# YMF_262.net
KiCad netlist of a schematic drawn in EAGLE
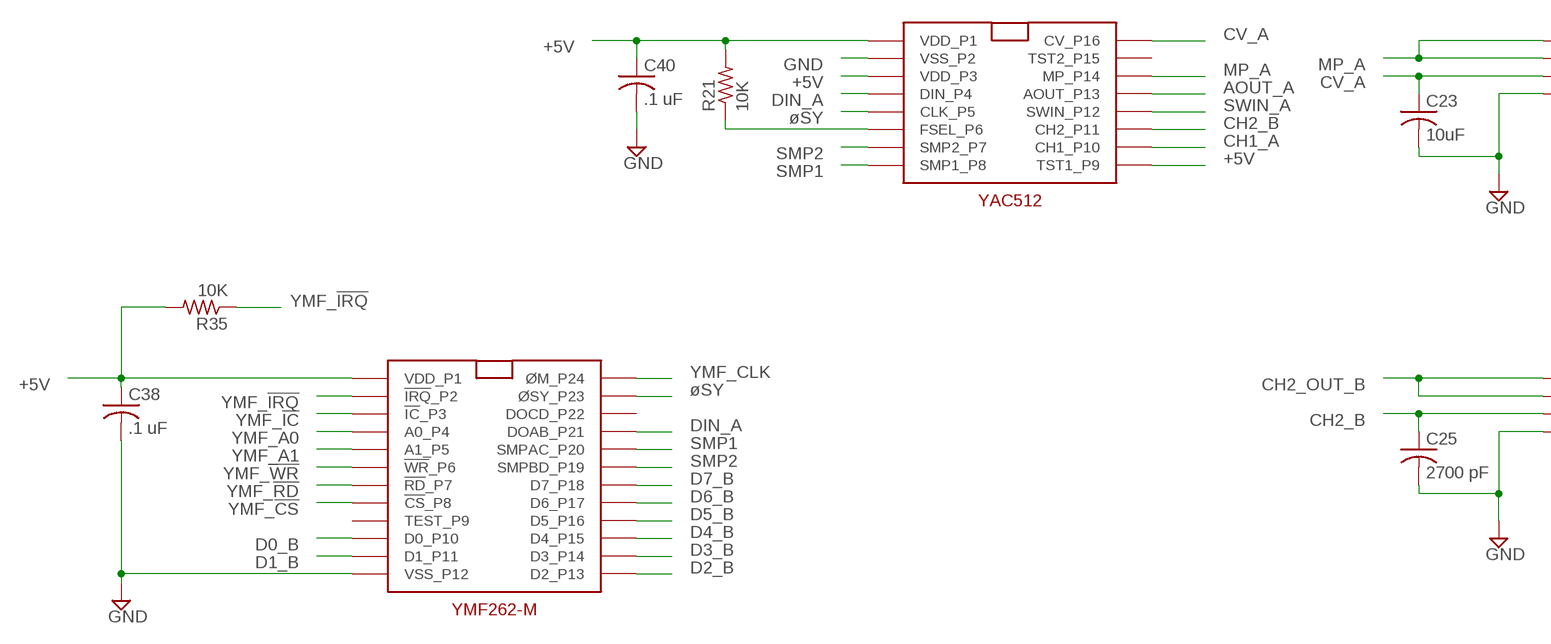
[diagram p0: schematic, sheet 1, part 1 of 2]
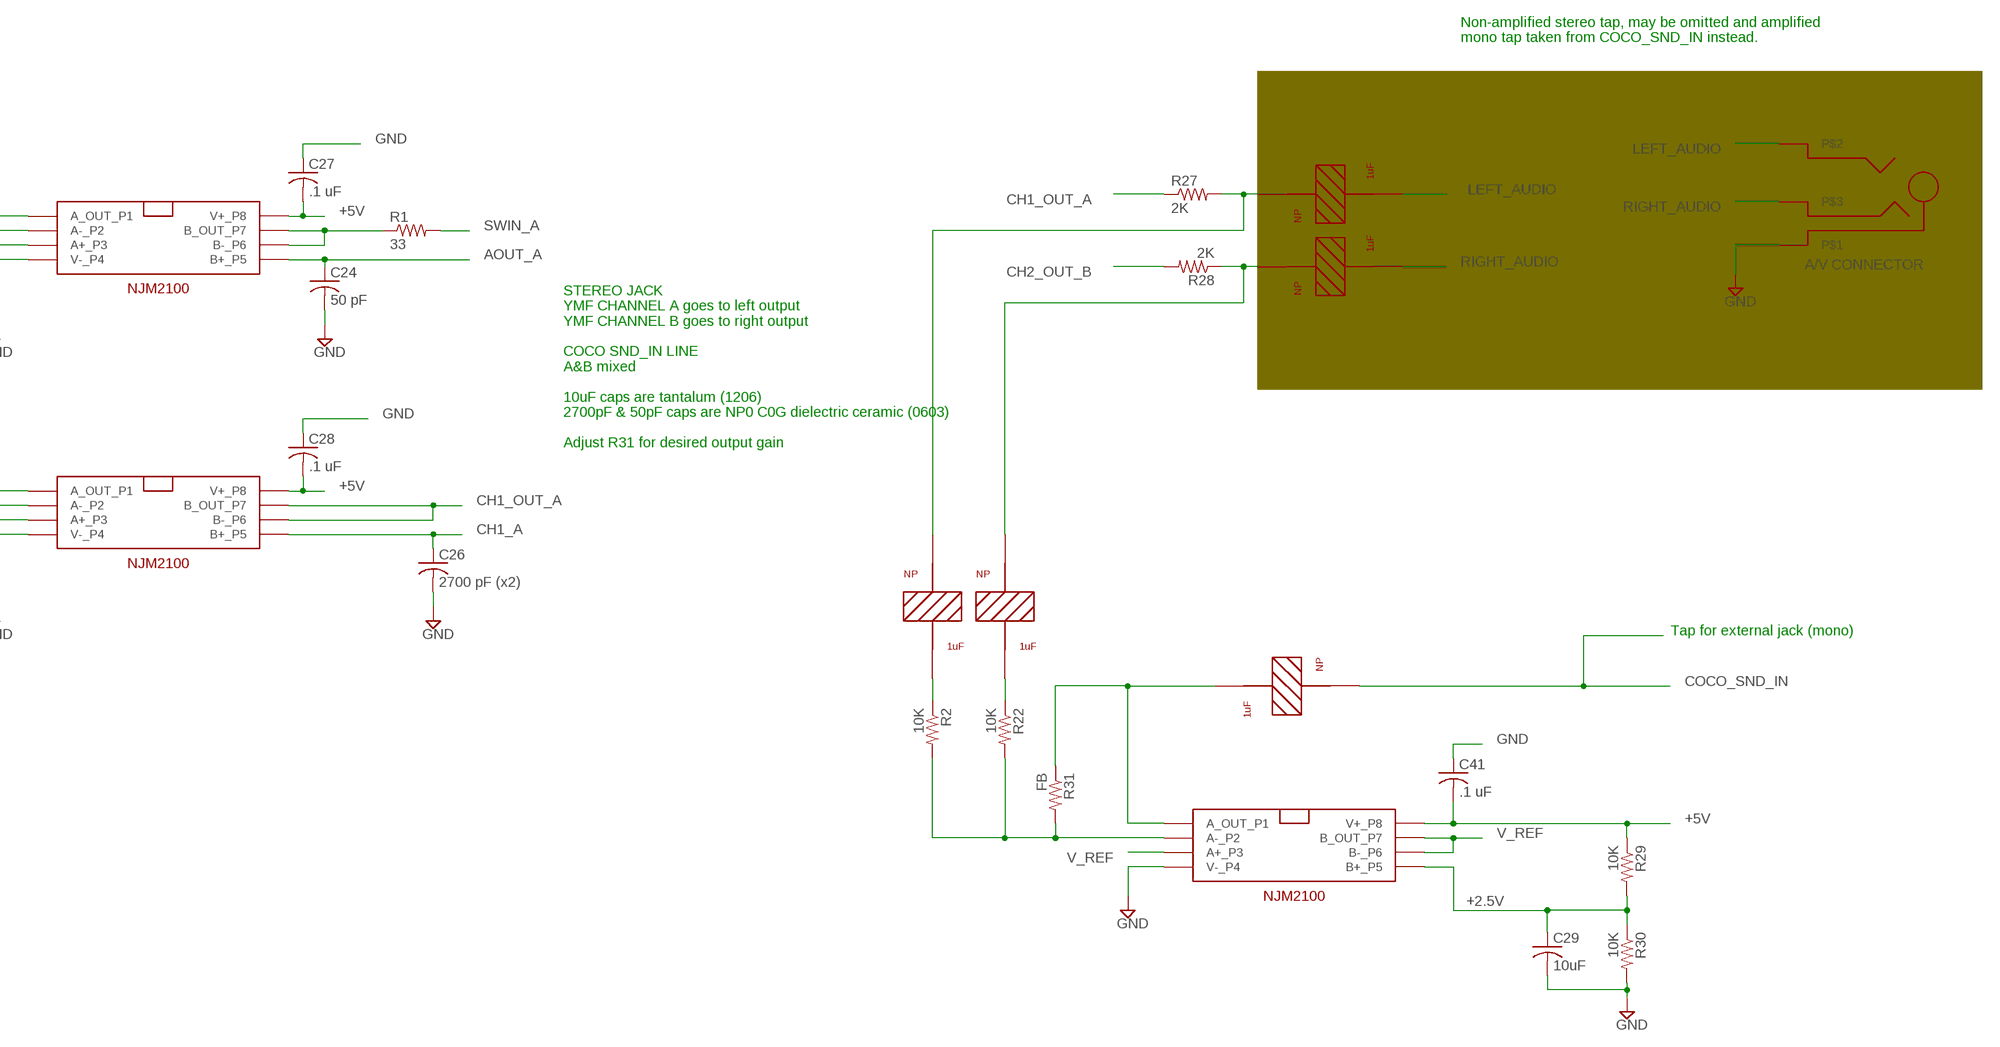
[diagram p1: schematic, sheet 1, part 2 of 2]

(export (version "E")
  (design (tool "Eeschema 10.0.6"))
  (components
    (comp (ref "C23")
      (value "10uF")
      (footprint "eagle-import:C1206")
      (libsource (lib "eagle-import") (part "C-USC1206"))
    )
    (comp (ref "C24")
      (value "50 pF")
      (footprint "eagle-import:C0603K")
      (libsource (lib "eagle-import") (part "C-USC0603K"))
    )
    (comp (ref "C25")
      (value "2700 pF")
      (footprint "eagle-import:C0603K")
      (libsource (lib "eagle-import") (part "C-USC0603K"))
    )
    (comp (ref "C26")
      (value "2700 pF (x2)")
      (footprint "eagle-import:C0603K")
      (libsource (lib "eagle-import") (part "C-USC0603K"))
    )
    (comp (ref "C27")
      (value ".1 uF")
      (footprint "eagle-import:C0603K")
      (libsource (lib "eagle-import") (part "C-USC0603K"))
    )
    (comp (ref "C28")
      (value ".1 uF")
      (footprint "eagle-import:C0603K")
      (libsource (lib "eagle-import") (part "C-USC0603K"))
    )
    (comp (ref "C29")
      (value "10uF")
      (footprint "eagle-import:C1206")
      (libsource (lib "eagle-import") (part "C-USC1206"))
    )
    (comp (ref "C38")
      (value ".1 uF")
      (footprint "eagle-import:C0603K")
      (libsource (lib "eagle-import") (part "C-USC0603K"))
    )
    (comp (ref "C40")
      (value ".1 uF")
      (footprint "eagle-import:C0603K")
      (libsource (lib "eagle-import") (part "C-USC0603K"))
    )
    (comp (ref "C41")
      (value ".1 uF")
      (footprint "eagle-import:C0603K")
      (libsource (lib "eagle-import") (part "C-USC0603K"))
    )
    (comp (ref "R1")
      (value "33")
      (footprint "eagle-import:R0805")
      (libsource (lib "eagle-import") (part "R-US_R0805"))
    )
    (comp (ref "R2")
      (value "10K")
      (footprint "eagle-import:R0805")
      (libsource (lib "eagle-import") (part "R-US_R0805"))
    )
    (comp (ref "R21")
      (value "10K")
      (footprint "eagle-import:M0805")
      (libsource (lib "eagle-import") (part "R-US_M0805"))
    )
    (comp (ref "R22")
      (value "10K")
      (footprint "eagle-import:R0805")
      (libsource (lib "eagle-import") (part "R-US_R0805"))
    )
    (comp (ref "R27")
      (value "2K")
      (footprint "eagle-import:R0805")
      (libsource (lib "eagle-import") (part "R-US_R0805"))
    )
    (comp (ref "R28")
      (value "2K")
      (footprint "eagle-import:R0805")
      (libsource (lib "eagle-import") (part "R-US_R0805"))
    )
    (comp (ref "R29")
      (value "10K")
      (footprint "eagle-import:R0805")
      (libsource (lib "eagle-import") (part "R-US_R0805"))
    )
    (comp (ref "R30")
      (value "10K")
      (footprint "eagle-import:R0805")
      (libsource (lib "eagle-import") (part "R-US_R0805"))
    )
    (comp (ref "R31")
      (value "FB")
      (footprint "eagle-import:R0805")
      (libsource (lib "eagle-import") (part "R-US_R0805"))
    )
    (comp (ref "R35")
      (value "10K")
      (footprint "eagle-import:M0805")
      (libsource (lib "eagle-import") (part "R-US_M0805"))
    )
    (comp (ref "U$1")
      (value "1uF")
      (footprint "eagle-import:NICHICON_SMT_CAP_4MM_NP")
      (libsource (lib "eagle-import") (part "NICHICON_SMT_CAP_4MM_NP"))
    )
    (comp (ref "U$2")
      (value "CUI-3543N")
      (footprint "eagle-import:CUI-3543N")
      (libsource (lib "eagle-import") (part "CUI-3543N"))
    )
    (comp (ref "U$3")
      (value "1uF")
      (footprint "eagle-import:NICHICON_SMT_CAP_4MM_NP")
      (libsource (lib "eagle-import") (part "NICHICON_SMT_CAP_4MM_NP"))
    )
    (comp (ref "U$15")
      (value "YMF262_M")
      (footprint "eagle-import:YMF262_M")
      (libsource (lib "eagle-import") (part "YMF262_M"))
    )
    (comp (ref "U$18")
      (value "YAC512")
      (footprint "eagle-import:YAC512")
      (libsource (lib "eagle-import") (part "YAC512"))
    )
    (comp (ref "U$19")
      (value "NJM2100_SSOP8")
      (footprint "eagle-import:NJM2100_SSOP8")
      (libsource (lib "eagle-import") (part "NJM2100_SSOP8"))
    )
    (comp (ref "U$20")
      (value "NJM2100_SSOP8")
      (footprint "eagle-import:NJM2100_SSOP8")
      (libsource (lib "eagle-import") (part "NJM2100_SSOP8"))
    )
    (comp (ref "U$21")
      (value "1uF")
      (footprint "eagle-import:NICHICON_SMT_CAP_4MM_NP")
      (libsource (lib "eagle-import") (part "NICHICON_SMT_CAP_4MM_NP"))
    )
    (comp (ref "U$25")
      (value "NJM2100_SSOP8")
      (footprint "eagle-import:NJM2100_SSOP8")
      (libsource (lib "eagle-import") (part "NJM2100_SSOP8"))
    )
    (comp (ref "U$26")
      (value "1uF")
      (footprint "eagle-import:NICHICON_SMT_CAP_4MM_NP")
      (libsource (lib "eagle-import") (part "NICHICON_SMT_CAP_4MM_NP"))
    )
    (comp (ref "U$27")
      (value "1uF")
      (footprint "eagle-import:NICHICON_SMT_CAP_4MM_NP")
      (libsource (lib "eagle-import") (part "NICHICON_SMT_CAP_4MM_NP"))
    )
  )
  (nets
    (net (code "1") (name "/+2.5V") (class "Default")
      (node (ref "C29") (pin "1") (pinfunction "1_1") (pintype "passive"))
      (node (ref "R29") (pin "2") (pinfunction "2_2") (pintype "passive"))
      (node (ref "R30") (pin "1") (pinfunction "1_1") (pintype "passive"))
      (node (ref "U$25") (pin "P$5") (pinfunction "B+_P5_P$5") (pintype "bidirectional"))
    )
    (net (code "2") (name "/+5V") (class "Default")
      (node (ref "C27") (pin "2") (pinfunction "2_2") (pintype "passive"))
      (node (ref "C28") (pin "2") (pinfunction "2_2") (pintype "passive"))
      (node (ref "C38") (pin "1") (pinfunction "1_1") (pintype "passive"))
      (node (ref "C40") (pin "1") (pinfunction "1_1") (pintype "passive"))
      (node (ref "C41") (pin "2") (pinfunction "2_2") (pintype "passive"))
      (node (ref "R21") (pin "2") (pinfunction "2_2") (pintype "passive"))
      (node (ref "R29") (pin "1") (pinfunction "1_1") (pintype "passive"))
      (node (ref "R35") (pin "2") (pinfunction "2_2") (pintype "passive"))
      (node (ref "U$15") (pin "P$1") (pinfunction "VDD_P1_P$1") (pintype "bidirectional"))
      (node (ref "U$18") (pin "P$1") (pinfunction "VDD_P1_P$1") (pintype "bidirectional"))
      (node (ref "U$18") (pin "P$3") (pinfunction "VDD_P3_P$3") (pintype "bidirectional"))
      (node (ref "U$18") (pin "P$9") (pinfunction "TST1_P9_P$9") (pintype "bidirectional"))
      (node (ref "U$19") (pin "P$8") (pinfunction "V+_P8_P$8") (pintype "bidirectional"))
      (node (ref "U$20") (pin "P$8") (pinfunction "V+_P8_P$8") (pintype "bidirectional"))
      (node (ref "U$25") (pin "P$8") (pinfunction "V+_P8_P$8") (pintype "bidirectional"))
    )
    (net (code "3") (name "/AOUT_A") (class "Default")
      (node (ref "C24") (pin "1") (pinfunction "1_1") (pintype "passive"))
      (node (ref "U$18") (pin "P$13") (pinfunction "AOUT_P13_P$13") (pintype "bidirectional"))
      (node (ref "U$19") (pin "P$5") (pinfunction "B+_P5_P$5") (pintype "bidirectional"))
    )
    (net (code "4") (name "/CH1_A") (class "Default")
      (node (ref "C26") (pin "1") (pinfunction "1_1") (pintype "passive"))
      (node (ref "U$18") (pin "P$10") (pinfunction "CH1_P10_P$10") (pintype "bidirectional"))
      (node (ref "U$20") (pin "P$5") (pinfunction "B+_P5_P$5") (pintype "bidirectional"))
    )
    (net (code "5") (name "/CH1_OUT_A") (class "Default")
      (node (ref "R27") (pin "1") (pinfunction "1_1") (pintype "passive"))
      (node (ref "U$20") (pin "P$6") (pinfunction "B-_P6_P$6") (pintype "bidirectional"))
      (node (ref "U$20") (pin "P$7") (pinfunction "B_OUT_P7_P$7") (pintype "bidirectional"))
    )
    (net (code "6") (name "/CH2_B") (class "Default")
      (node (ref "C25") (pin "1") (pinfunction "1_1") (pintype "passive"))
      (node (ref "U$18") (pin "P$11") (pinfunction "CH2_P11_P$11") (pintype "bidirectional"))
      (node (ref "U$20") (pin "P$3") (pinfunction "A+_P3_P$3") (pintype "bidirectional"))
    )
    (net (code "7") (name "/CH2_OUT_B") (class "Default")
      (node (ref "R28") (pin "2") (pinfunction "2_2") (pintype "passive"))
      (node (ref "U$20") (pin "P$1") (pinfunction "A_OUT_P1_P$1") (pintype "bidirectional"))
      (node (ref "U$20") (pin "P$2") (pinfunction "A-_P2_P$2") (pintype "bidirectional"))
    )
    (net (code "8") (name "/COCO_SND_IN") (class "Default")
      (node (ref "U$1") (pin "P$1") (pinfunction "P$1_P$1") (pintype "bidirectional"))
    )
    (net (code "9") (name "/CV_A") (class "Default")
      (node (ref "C23") (pin "1") (pinfunction "1_1") (pintype "passive"))
      (node (ref "U$18") (pin "P$16") (pinfunction "CV_P16_P$16") (pintype "bidirectional"))
      (node (ref "U$19") (pin "P$3") (pinfunction "A+_P3_P$3") (pintype "bidirectional"))
    )
    (net (code "10") (name "/D0_B") (class "Default")
      (node (ref "U$15") (pin "P$10") (pinfunction "D0_P10_P$10") (pintype "bidirectional"))
    )
    (net (code "11") (name "/D1_B") (class "Default")
      (node (ref "U$15") (pin "P$11") (pinfunction "D1_P11_P$11") (pintype "bidirectional"))
    )
    (net (code "12") (name "/D2_B") (class "Default")
      (node (ref "U$15") (pin "P$13") (pinfunction "D2_P13_P$13") (pintype "bidirectional"))
    )
    (net (code "13") (name "/D3_B") (class "Default")
      (node (ref "U$15") (pin "P$14") (pinfunction "D3_P14_P$14") (pintype "bidirectional"))
    )
    (net (code "14") (name "/D4_B") (class "Default")
      (node (ref "U$15") (pin "P$15") (pinfunction "D4_P15_P$15") (pintype "bidirectional"))
    )
    (net (code "15") (name "/D5_B") (class "Default")
      (node (ref "U$15") (pin "P$16") (pinfunction "D5_P16_P$16") (pintype "bidirectional"))
    )
    (net (code "16") (name "/D6_B") (class "Default")
      (node (ref "U$15") (pin "P$17") (pinfunction "D6_P17_P$17") (pintype "bidirectional"))
    )
    (net (code "17") (name "/D7_B") (class "Default")
      (node (ref "U$15") (pin "P$18") (pinfunction "D7_P18_P$18") (pintype "bidirectional"))
    )
    (net (code "18") (name "/DIN_A") (class "Default")
      (node (ref "U$15") (pin "P$21") (pinfunction "DOAB_P21_P$21") (pintype "bidirectional"))
      (node (ref "U$18") (pin "P$4") (pinfunction "DIN_P4_P$4") (pintype "bidirectional"))
    )
    (net (code "19") (name "/LEFT_AUDIO") (class "Default")
      (node (ref "U$2") (pin "2") (pinfunction "P$2_2") (pintype "bidirectional"))
      (node (ref "U$26") (pin "P$2") (pinfunction "P$2_P$2") (pintype "bidirectional"))
    )
    (net (code "20") (name "/MP_A") (class "Default")
      (node (ref "U$18") (pin "P$14") (pinfunction "MP_P14_P$14") (pintype "bidirectional"))
      (node (ref "U$19") (pin "P$1") (pinfunction "A_OUT_P1_P$1") (pintype "bidirectional"))
      (node (ref "U$19") (pin "P$2") (pinfunction "A-_P2_P$2") (pintype "bidirectional"))
    )
    (net (code "21") (name "/RIGHT_AUDIO") (class "Default")
      (node (ref "U$2") (pin "3") (pinfunction "P$3_3") (pintype "bidirectional"))
      (node (ref "U$27") (pin "P$2") (pinfunction "P$2_P$2") (pintype "bidirectional"))
    )
    (net (code "22") (name "/SMP1") (class "Default")
      (node (ref "U$15") (pin "P$20") (pinfunction "SMPAC_P20_P$20") (pintype "bidirectional"))
      (node (ref "U$18") (pin "P$8") (pinfunction "SMP1_P8_P$8") (pintype "bidirectional"))
    )
    (net (code "23") (name "/SMP2") (class "Default")
      (node (ref "U$15") (pin "P$19") (pinfunction "SMPBD_P19_P$19") (pintype "bidirectional"))
      (node (ref "U$18") (pin "P$7") (pinfunction "SMP2_P7_P$7") (pintype "bidirectional"))
    )
    (net (code "24") (name "/SWIN_A") (class "Default")
      (node (ref "R1") (pin "2") (pinfunction "2_2") (pintype "passive"))
      (node (ref "U$18") (pin "P$12") (pinfunction "SWIN_P12_P$12") (pintype "bidirectional"))
    )
    (net (code "25") (name "/V_REF") (class "Default")
      (node (ref "U$25") (pin "P$3") (pinfunction "A+_P3_P$3") (pintype "bidirectional"))
      (node (ref "U$25") (pin "P$6") (pinfunction "B-_P6_P$6") (pintype "bidirectional"))
      (node (ref "U$25") (pin "P$7") (pinfunction "B_OUT_P7_P$7") (pintype "bidirectional"))
    )
    (net (code "26") (name "/YMF_A0") (class "Default")
      (node (ref "U$15") (pin "P$4") (pinfunction "A0_P4_P$4") (pintype "bidirectional"))
    )
    (net (code "27") (name "/YMF_A1") (class "Default")
      (node (ref "U$15") (pin "P$5") (pinfunction "A1_P5_P$5") (pintype "bidirectional"))
    )
    (net (code "28") (name "/YMF_CLK") (class "Default")
      (node (ref "U$15") (pin "P$24") (pinfunction "ØM_P24_P$24") (pintype "bidirectional"))
    )
    (net (code "29") (name "/YMF_~{CS}") (class "Default")
      (node (ref "U$15") (pin "P$8") (pinfunction "~{CS}_P8_P$8") (pintype "bidirectional"))
    )
    (net (code "30") (name "/YMF_~{IC}") (class "Default")
      (node (ref "U$15") (pin "P$3") (pinfunction "~{IC}_P3_P$3") (pintype "bidirectional"))
    )
    (net (code "31") (name "/YMF_~{IRQ}") (class "Default")
      (node (ref "R35") (pin "1") (pinfunction "1_1") (pintype "passive"))
      (node (ref "U$15") (pin "P$2") (pinfunction "~{IRQ}_P2_P$2") (pintype "bidirectional"))
    )
    (net (code "32") (name "/YMF_~{RD}") (class "Default")
      (node (ref "U$15") (pin "P$7") (pinfunction "~{RD}_P7_P$7") (pintype "bidirectional"))
    )
    (net (code "33") (name "/YMF_~{WR}") (class "Default")
      (node (ref "U$15") (pin "P$6") (pinfunction "~{WR}_P6_P$6") (pintype "bidirectional"))
    )
    (net (code "34") (name "/øSY") (class "Default")
      (node (ref "U$15") (pin "P$23") (pinfunction "ØSY_P23_P$23") (pintype "bidirectional"))
      (node (ref "U$18") (pin "P$5") (pinfunction "CLK_P5_P$5") (pintype "bidirectional"))
    )
    (net (code "35") (name "GND") (class "Default")
      (node (ref "C23") (pin "2") (pinfunction "2_2") (pintype "passive"))
      (node (ref "C24") (pin "2") (pinfunction "2_2") (pintype "passive"))
      (node (ref "C25") (pin "2") (pinfunction "2_2") (pintype "passive"))
      (node (ref "C26") (pin "2") (pinfunction "2_2") (pintype "passive"))
      (node (ref "C27") (pin "1") (pinfunction "1_1") (pintype "passive"))
      (node (ref "C28") (pin "1") (pinfunction "1_1") (pintype "passive"))
      (node (ref "C29") (pin "2") (pinfunction "2_2") (pintype "passive"))
      (node (ref "C38") (pin "2") (pinfunction "2_2") (pintype "passive"))
      (node (ref "C40") (pin "2") (pinfunction "2_2") (pintype "passive"))
      (node (ref "C41") (pin "1") (pinfunction "1_1") (pintype "passive"))
      (node (ref "R30") (pin "2") (pinfunction "2_2") (pintype "passive"))
      (node (ref "U$15") (pin "P$12") (pinfunction "VSS_P12_P$12") (pintype "bidirectional"))
      (node (ref "U$18") (pin "P$2") (pinfunction "VSS_P2_P$2") (pintype "bidirectional"))
      (node (ref "U$19") (pin "P$4") (pinfunction "V-_P4_P$4") (pintype "bidirectional"))
      (node (ref "U$2") (pin "1") (pinfunction "P$1_1") (pintype "bidirectional"))
      (node (ref "U$20") (pin "P$4") (pinfunction "V-_P4_P$4") (pintype "bidirectional"))
      (node (ref "U$25") (pin "P$4") (pinfunction "V-_P4_P$4") (pintype "bidirectional"))
    )
    (net (code "36") (name "Net-(R2-Pad1)") (class "Default")
      (node (ref "R2") (pin "1") (pinfunction "1_1") (pintype "passive"))
      (node (ref "U$3") (pin "P$2") (pinfunction "P$2_P$2") (pintype "bidirectional"))
    )
    (net (code "37") (name "Net-(R22-Pad1)") (class "Default")
      (node (ref "R22") (pin "1") (pinfunction "1_1") (pintype "passive"))
      (node (ref "U$21") (pin "P$2") (pinfunction "P$2_P$2") (pintype "bidirectional"))
    )
    (net (code "38") (name "Net-(R27-Pad2)") (class "Default")
      (node (ref "R27") (pin "2") (pinfunction "2_2") (pintype "passive"))
      (node (ref "U$26") (pin "P$1") (pinfunction "P$1_P$1") (pintype "bidirectional"))
      (node (ref "U$3") (pin "P$1") (pinfunction "P$1_P$1") (pintype "bidirectional"))
    )
    (net (code "39") (name "Net-(R28-Pad1)") (class "Default")
      (node (ref "R28") (pin "1") (pinfunction "1_1") (pintype "passive"))
      (node (ref "U$21") (pin "P$1") (pinfunction "P$1_P$1") (pintype "bidirectional"))
      (node (ref "U$27") (pin "P$1") (pinfunction "P$1_P$1") (pintype "bidirectional"))
    )
    (net (code "40") (name "Net-(U$18-FSEL_P6)") (class "Default")
      (node (ref "R21") (pin "1") (pinfunction "1_1") (pintype "passive"))
      (node (ref "U$18") (pin "P$6") (pinfunction "FSEL_P6_P$6") (pintype "bidirectional"))
    )
    (net (code "41") (name "Net-(U$19-B-_P6)") (class "Default")
      (node (ref "R1") (pin "1") (pinfunction "1_1") (pintype "passive"))
      (node (ref "U$19") (pin "P$6") (pinfunction "B-_P6_P$6") (pintype "bidirectional"))
      (node (ref "U$19") (pin "P$7") (pinfunction "B_OUT_P7_P$7") (pintype "bidirectional"))
    )
    (net (code "42") (name "Net-(U$25-A-_P2)") (class "Default")
      (node (ref "R2") (pin "2") (pinfunction "2_2") (pintype "passive"))
      (node (ref "R22") (pin "2") (pinfunction "2_2") (pintype "passive"))
      (node (ref "R31") (pin "2") (pinfunction "2_2") (pintype "passive"))
      (node (ref "U$25") (pin "P$2") (pinfunction "A-_P2_P$2") (pintype "bidirectional"))
    )
    (net (code "43") (name "Net-(U$25-A_OUT_P1)") (class "Default")
      (node (ref "R31") (pin "1") (pinfunction "1_1") (pintype "passive"))
      (node (ref "U$1") (pin "P$2") (pinfunction "P$2_P$2") (pintype "bidirectional"))
      (node (ref "U$25") (pin "P$1") (pinfunction "A_OUT_P1_P$1") (pintype "bidirectional"))
    )
    (net (code "44") (name "unconnected-(U$15-DOCD_P22-PadP$22)") (class "Default")
      (node (ref "U$15") (pin "P$22") (pinfunction "DOCD_P22_P$22") (pintype "bidirectional"))
    )
    (net (code "45") (name "unconnected-(U$15-TEST_P9-PadP$9)") (class "Default")
      (node (ref "U$15") (pin "P$9") (pinfunction "TEST_P9_P$9") (pintype "bidirectional"))
    )
    (net (code "46") (name "unconnected-(U$18-TST2_P15-PadP$15)") (class "Default")
      (node (ref "U$18") (pin "P$15") (pinfunction "TST2_P15_P$15") (pintype "bidirectional"))
    )
  )
)
